# Sensors.net
KiCad netlist of a schematic drawn in Altium Designer
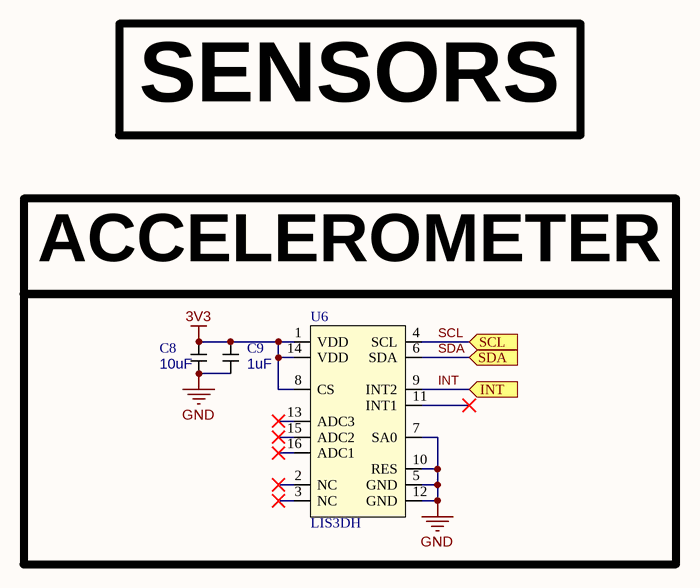
[diagram p0: Sensors.SchDoc]

(export (version "E")
  (design (tool "Eeschema 10.0.6"))
  (components
    (comp (ref "C8")
      (value "10uF")
      (footprint "CAP_0402_HIGH")
      (description "0402 Capacitor")
      (libsource (lib "smLib") (part "Capacitor_0402"))
    )
    (comp (ref "C9")
      (value "1uF")
      (footprint "CAP_0402_HIGH")
      (description "0402 Capacitor")
      (libsource (lib "smLib") (part "Capacitor_0402"))
    )
    (comp (ref "U6")
      (value "LIS3DH")
      (footprint "LIS3DH")
      (description "LIS3DH ACCEL 2-16G I2C/SPI 16LGA")
      (libsource (lib "smLib") (part "LIS3DH"))
    )
  )
  (nets
    (net (code "1") (name "/INT") (class "Default")
      (node (ref "U6") (pin "9") (pinfunction "INT2_9") (pintype "passive"))
    )
    (net (code "2") (name "/SCL") (class "Default")
      (node (ref "U6") (pin "4") (pinfunction "SCL_4") (pintype "passive"))
    )
    (net (code "3") (name "/SDA") (class "Default")
      (node (ref "U6") (pin "6") (pinfunction "SDA_6") (pintype "passive"))
    )
    (net (code "4") (name "3V3") (class "Default")
      (node (ref "C8") (pin "2") (pinfunction "2_2") (pintype "passive"))
      (node (ref "C9") (pin "2") (pinfunction "2_2") (pintype "passive"))
      (node (ref "U6") (pin "1") (pinfunction "VDD_1") (pintype "passive"))
      (node (ref "U6") (pin "14") (pinfunction "VDD_14") (pintype "passive"))
      (node (ref "U6") (pin "8") (pinfunction "CS_8") (pintype "passive"))
    )
    (net (code "5") (name "GND") (class "Default")
      (node (ref "C8") (pin "1") (pinfunction "1_1") (pintype "passive"))
      (node (ref "C9") (pin "1") (pinfunction "1_1") (pintype "passive"))
      (node (ref "U6") (pin "10") (pinfunction "RES_10") (pintype "passive"))
      (node (ref "U6") (pin "12") (pinfunction "GND_12") (pintype "passive"))
      (node (ref "U6") (pin "5") (pinfunction "GND_5") (pintype "passive"))
      (node (ref "U6") (pin "7") (pinfunction "SA0_7") (pintype "passive"))
    )
    (net (code "6") (name "unconnected-(U6-ADC1-Pad16)") (class "Default")
      (node (ref "U6") (pin "16") (pinfunction "ADC1_16") (pintype "passive+no_connect"))
    )
    (net (code "7") (name "unconnected-(U6-ADC2-Pad15)") (class "Default")
      (node (ref "U6") (pin "15") (pinfunction "ADC2_15") (pintype "passive+no_connect"))
    )
    (net (code "8") (name "unconnected-(U6-ADC3-Pad13)") (class "Default")
      (node (ref "U6") (pin "13") (pinfunction "ADC3_13") (pintype "passive+no_connect"))
    )
    (net (code "9") (name "unconnected-(U6-INT1-Pad11)") (class "Default")
      (node (ref "U6") (pin "11") (pinfunction "INT1_11") (pintype "passive+no_connect"))
    )
    (net (code "10") (name "unconnected-(U6-NC-Pad2)") (class "Default")
      (node (ref "U6") (pin "2") (pinfunction "NC_2") (pintype "passive+no_connect"))
    )
    (net (code "11") (name "unconnected-(U6-NC-Pad3)") (class "Default")
      (node (ref "U6") (pin "3") (pinfunction "NC_3") (pintype "passive+no_connect"))
    )
  )
)
